# midi10trigger.net
KiCad netlist of a schematic drawn in EAGLE
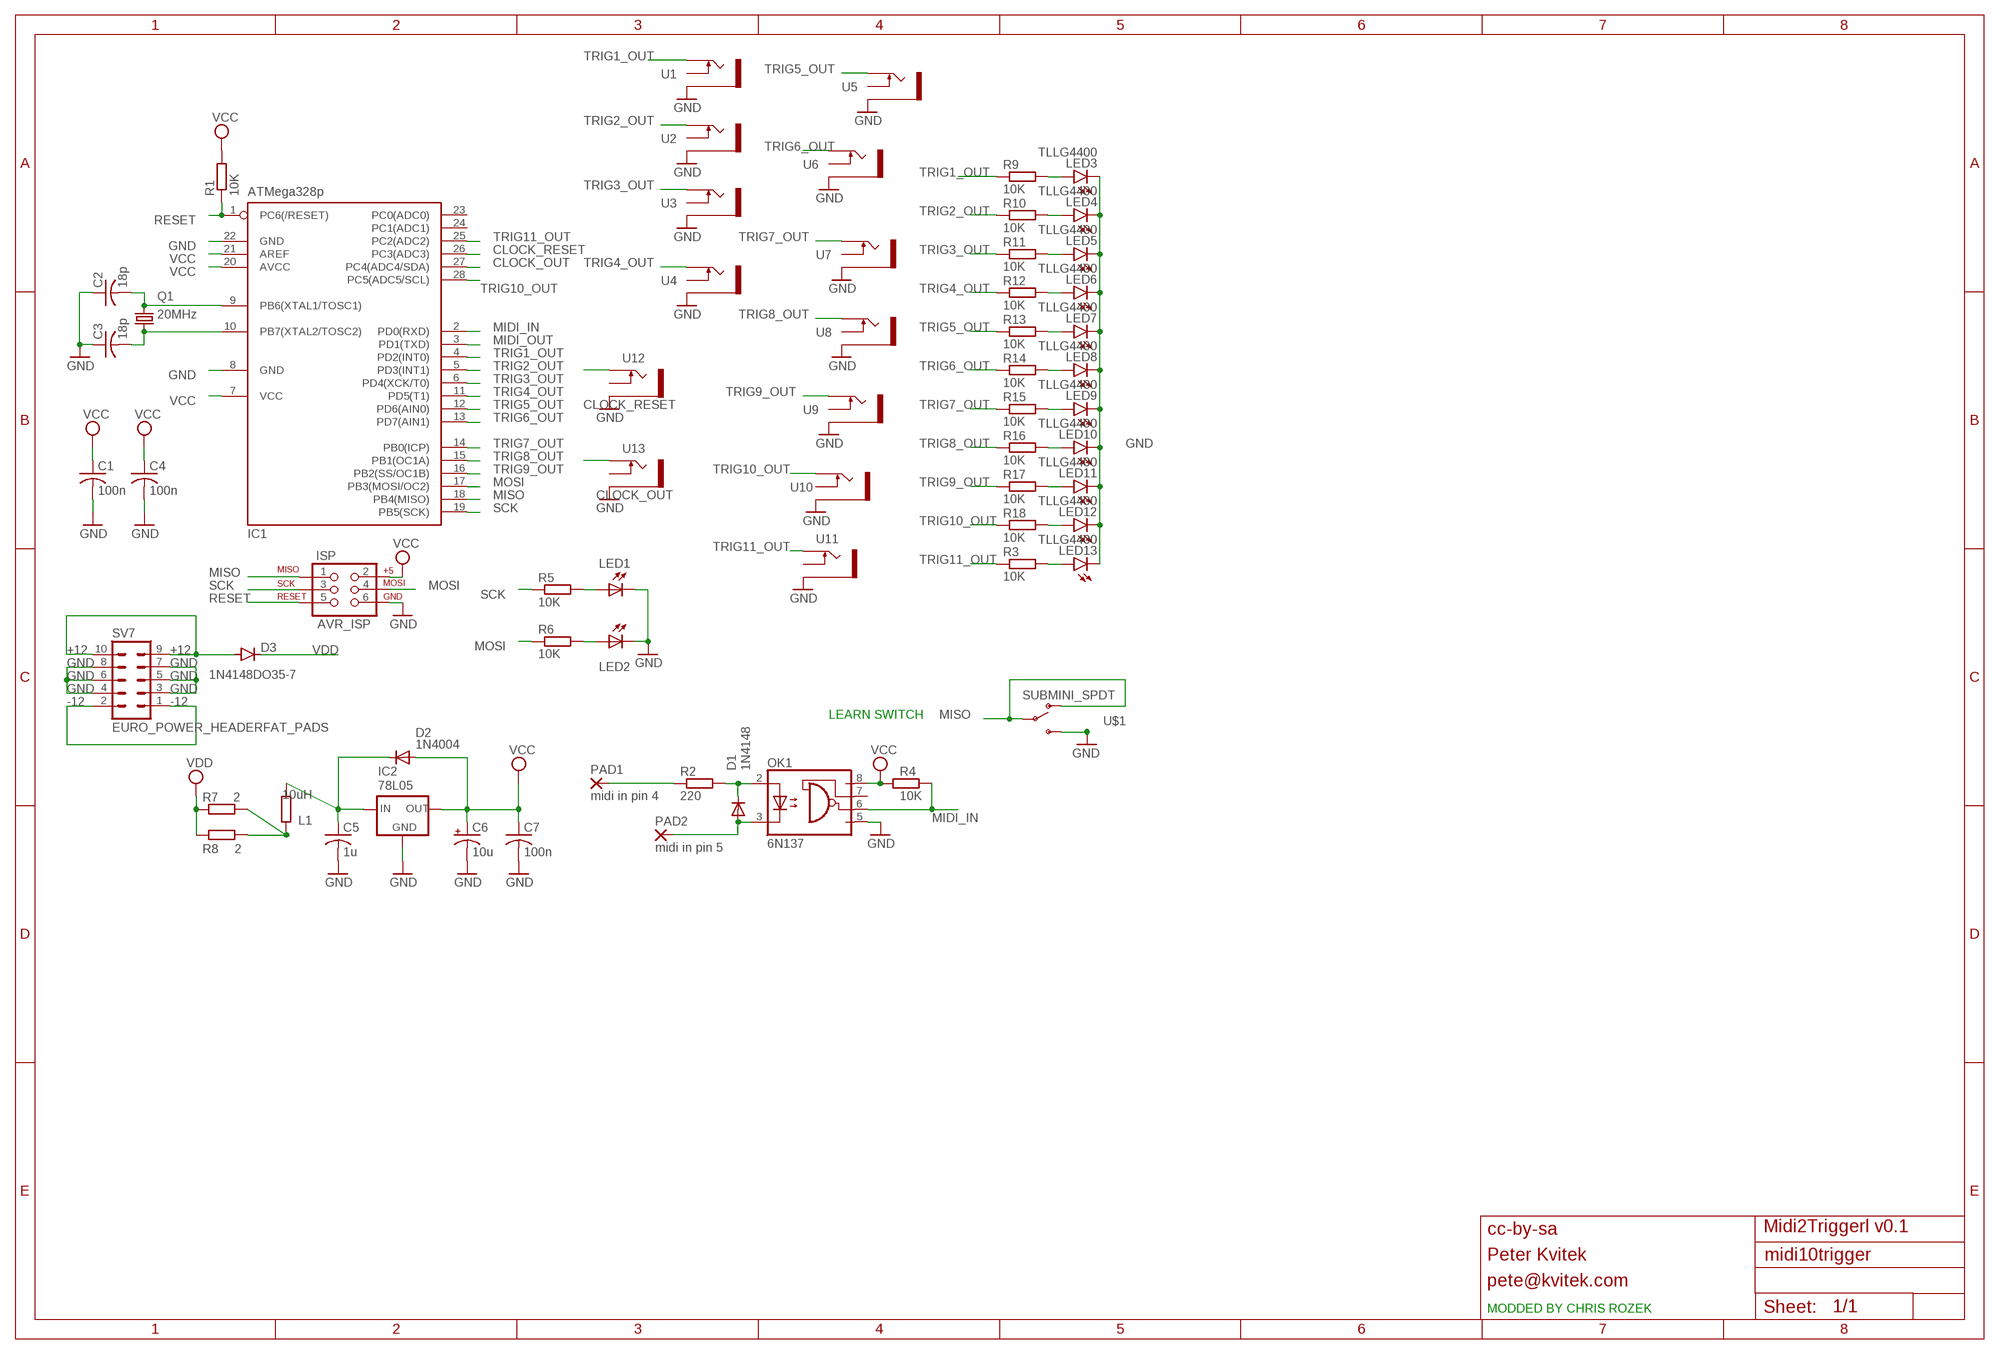
[diagram p0: schematic, sheet 1]

(export (version "E")
  (design (tool "Eeschema 10.0.6"))
  (components
    (comp (ref "C1")
      (value "100n")
      (footprint "eagle-import:C025-025X050")
      (libsource (lib "eagle-import") (part "C-US025-025X050"))
    )
    (comp (ref "C2")
      (value "18p")
      (footprint "eagle-import:C025-025X050")
      (libsource (lib "eagle-import") (part "C-US025-025X050"))
    )
    (comp (ref "C3")
      (value "18p")
      (footprint "eagle-import:C025-025X050")
      (libsource (lib "eagle-import") (part "C-US025-025X050"))
    )
    (comp (ref "C4")
      (value "100n")
      (footprint "eagle-import:C025-025X050")
      (libsource (lib "eagle-import") (part "C-US025-025X050"))
    )
    (comp (ref "C5")
      (value "1u")
      (footprint "eagle-import:C025-025X050")
      (libsource (lib "eagle-import") (part "C-US025-025X050"))
    )
    (comp (ref "C6")
      (value "10u")
      (footprint "eagle-import:E2,5-5")
      (libsource (lib "eagle-import") (part "CPOL-USE2.5-5"))
    )
    (comp (ref "C7")
      (value "100n")
      (footprint "eagle-import:C025-025X050")
      (libsource (lib "eagle-import") (part "C-US025-025X050"))
    )
    (comp (ref "D1")
      (value "1N4148")
      (footprint "eagle-import:D-5")
      (libsource (lib "eagle-import") (part "DIODE-D-5"))
    )
    (comp (ref "D2")
      (value "1N4004")
      (footprint "eagle-import:DO41-10")
      (libsource (lib "eagle-import") (part "1N4004"))
    )
    (comp (ref "D3")
      (value "1N4148DO35-7")
      (footprint "eagle-import:DO35-7")
      (libsource (lib "eagle-import") (part "1N4148DO35-7"))
    )
    (comp (ref "IC1")
      (value "ATMega328p")
      (footprint "eagle-import:DIL28-3")
      (libsource (lib "eagle-import") (part "MEGA8-P"))
    )
    (comp (ref "IC2")
      (value "78L05")
      (footprint "eagle-import:78LXX")
      (libsource (lib "eagle-import") (part "78LXX"))
    )
    (comp (ref "ISP")
      (value "AVR_ISP")
      (footprint "eagle-import:2X3")
      (libsource (lib "eagle-import") (part "AVR_SPI_PRG_6PTH"))
    )
    (comp (ref "L1")
      (value "10uH")
      (footprint "eagle-import:VERTICAL_RESISTOR")
      (libsource (lib "eagle-import") (part "RESISTORVERTICAL"))
    )
    (comp (ref "LED1")
      (value "LED3MM")
      (footprint "eagle-import:LED3MM")
      (libsource (lib "eagle-import") (part "LED3MM"))
    )
    (comp (ref "LED2")
      (value "LED3MM")
      (footprint "eagle-import:LED3MM")
      (libsource (lib "eagle-import") (part "LED3MM"))
    )
    (comp (ref "LED3")
      (value "TLLG4400")
      (footprint "eagle-import:LED3MM")
      (fields (field (name "MF") "VISHAY SEMICONDUCTOR"))
      (libsource (lib "eagle-import") (part "TLLG4400"))
    )
    (comp (ref "LED4")
      (value "TLLG4400")
      (footprint "eagle-import:LED3MM")
      (fields (field (name "MF") "VISHAY SEMICONDUCTOR"))
      (libsource (lib "eagle-import") (part "TLLG4400"))
    )
    (comp (ref "LED5")
      (value "TLLG4400")
      (footprint "eagle-import:LED3MM")
      (fields (field (name "MF") "VISHAY SEMICONDUCTOR"))
      (libsource (lib "eagle-import") (part "TLLG4400"))
    )
    (comp (ref "LED6")
      (value "TLLG4400")
      (footprint "eagle-import:LED3MM")
      (fields (field (name "MF") "VISHAY SEMICONDUCTOR"))
      (libsource (lib "eagle-import") (part "TLLG4400"))
    )
    (comp (ref "LED7")
      (value "TLLG4400")
      (footprint "eagle-import:LED3MM")
      (fields (field (name "MF") "VISHAY SEMICONDUCTOR"))
      (libsource (lib "eagle-import") (part "TLLG4400"))
    )
    (comp (ref "LED8")
      (value "TLLG4400")
      (footprint "eagle-import:LED3MM")
      (fields (field (name "MF") "VISHAY SEMICONDUCTOR"))
      (libsource (lib "eagle-import") (part "TLLG4400"))
    )
    (comp (ref "LED9")
      (value "TLLG4400")
      (footprint "eagle-import:LED3MM")
      (fields (field (name "MF") "VISHAY SEMICONDUCTOR"))
      (libsource (lib "eagle-import") (part "TLLG4400"))
    )
    (comp (ref "LED10")
      (value "TLLG4400")
      (footprint "eagle-import:LED3MM")
      (fields (field (name "MF") "VISHAY SEMICONDUCTOR"))
      (libsource (lib "eagle-import") (part "TLLG4400"))
    )
    (comp (ref "LED11")
      (value "TLLG4400")
      (footprint "eagle-import:LED3MM")
      (fields (field (name "MF") "VISHAY SEMICONDUCTOR"))
      (libsource (lib "eagle-import") (part "TLLG4400"))
    )
    (comp (ref "LED12")
      (value "TLLG4400")
      (footprint "eagle-import:LED3MM")
      (fields (field (name "MF") "VISHAY SEMICONDUCTOR"))
      (libsource (lib "eagle-import") (part "TLLG4400"))
    )
    (comp (ref "LED13")
      (value "TLLG4400")
      (footprint "eagle-import:LED3MM")
      (fields (field (name "MF") "VISHAY SEMICONDUCTOR"))
      (libsource (lib "eagle-import") (part "TLLG4400"))
    )
    (comp (ref "OK1")
      (value "6N137")
      (footprint "eagle-import:DIL08")
      (libsource (lib "eagle-import") (part "6N137"))
    )
    (comp (ref "PAD1")
      (value "midi in pin 4")
      (footprint "eagle-import:2,54_1,1")
      (libsource (lib "eagle-import") (part "2,54/1,1"))
    )
    (comp (ref "PAD2")
      (value "midi in pin 5")
      (footprint "eagle-import:2,54_1,1")
      (libsource (lib "eagle-import") (part "2,54/1,1"))
    )
    (comp (ref "Q1")
      (value "20MHz")
      (footprint "eagle-import:HC49U-V")
      (libsource (lib "eagle-import") (part "CRYSTALHC49U-V"))
    )
    (comp (ref "R1")
      (value "10K")
      (footprint "eagle-import:VERTICAL_RESISTOR")
      (libsource (lib "eagle-import") (part "RESISTORVERTICAL"))
    )
    (comp (ref "R2")
      (value "220")
      (footprint "eagle-import:VERTICAL_RESISTOR")
      (libsource (lib "eagle-import") (part "RESISTORVERTICAL"))
    )
    (comp (ref "R3")
      (value "10K")
      (footprint "eagle-import:VERTICAL_RESISTOR")
      (libsource (lib "eagle-import") (part "RESISTORVERTICAL"))
    )
    (comp (ref "R4")
      (value "10K")
      (footprint "eagle-import:VERTICAL_RESISTOR")
      (libsource (lib "eagle-import") (part "RESISTORVERTICAL"))
    )
    (comp (ref "R5")
      (value "10K")
      (footprint "eagle-import:VERTICAL_RESISTOR")
      (libsource (lib "eagle-import") (part "RESISTORVERTICAL"))
    )
    (comp (ref "R6")
      (value "10K")
      (footprint "eagle-import:VERTICAL_RESISTOR")
      (libsource (lib "eagle-import") (part "RESISTORVERTICAL"))
    )
    (comp (ref "R7")
      (value "2")
      (footprint "eagle-import:VERTICAL_RESISTOR")
      (libsource (lib "eagle-import") (part "RESISTORVERTICAL"))
    )
    (comp (ref "R8")
      (value "2")
      (footprint "eagle-import:VERTICAL_RESISTOR")
      (libsource (lib "eagle-import") (part "RESISTORVERTICAL"))
    )
    (comp (ref "R9")
      (value "10K")
      (footprint "eagle-import:VERTICAL_RESISTOR")
      (libsource (lib "eagle-import") (part "RESISTORVERTICAL"))
    )
    (comp (ref "R10")
      (value "10K")
      (footprint "eagle-import:VERTICAL_RESISTOR")
      (libsource (lib "eagle-import") (part "RESISTORVERTICAL"))
    )
    (comp (ref "R11")
      (value "10K")
      (footprint "eagle-import:VERTICAL_RESISTOR")
      (libsource (lib "eagle-import") (part "RESISTORVERTICAL"))
    )
    (comp (ref "R12")
      (value "10K")
      (footprint "eagle-import:VERTICAL_RESISTOR")
      (libsource (lib "eagle-import") (part "RESISTORVERTICAL"))
    )
    (comp (ref "R13")
      (value "10K")
      (footprint "eagle-import:VERTICAL_RESISTOR")
      (libsource (lib "eagle-import") (part "RESISTORVERTICAL"))
    )
    (comp (ref "R14")
      (value "10K")
      (footprint "eagle-import:VERTICAL_RESISTOR")
      (libsource (lib "eagle-import") (part "RESISTORVERTICAL"))
    )
    (comp (ref "R15")
      (value "10K")
      (footprint "eagle-import:VERTICAL_RESISTOR")
      (libsource (lib "eagle-import") (part "RESISTORVERTICAL"))
    )
    (comp (ref "R16")
      (value "10K")
      (footprint "eagle-import:VERTICAL_RESISTOR")
      (libsource (lib "eagle-import") (part "RESISTORVERTICAL"))
    )
    (comp (ref "R17")
      (value "10K")
      (footprint "eagle-import:VERTICAL_RESISTOR")
      (libsource (lib "eagle-import") (part "RESISTORVERTICAL"))
    )
    (comp (ref "R18")
      (value "10K")
      (footprint "eagle-import:VERTICAL_RESISTOR")
      (libsource (lib "eagle-import") (part "RESISTORVERTICAL"))
    )
    (comp (ref "SV7")
      (value "EURO_POWER_HEADERFAT_PADS")
      (footprint "eagle-import:EURO_PWR_HEADER_FAT")
      (libsource (lib "eagle-import") (part "EURO_POWER_HEADERFAT_PADS"))
    )
    (comp (ref "U$1")
      (value "SUBMINI_SPDT")
      (footprint "eagle-import:SUBMINI_TOGGLE")
      (libsource (lib "eagle-import") (part "SUBMINI_SPDT"))
    )
    (comp (ref "U1")
      (value "THONKICONNNEW")
      (footprint "eagle-import:WQP-PJ301M-12_JACK")
      (libsource (lib "eagle-import") (part "THONKICONNNEW"))
    )
    (comp (ref "U2")
      (value "THONKICONNNEW")
      (footprint "eagle-import:WQP-PJ301M-12_JACK")
      (libsource (lib "eagle-import") (part "THONKICONNNEW"))
    )
    (comp (ref "U3")
      (value "THONKICONNNEW")
      (footprint "eagle-import:WQP-PJ301M-12_JACK")
      (libsource (lib "eagle-import") (part "THONKICONNNEW"))
    )
    (comp (ref "U4")
      (value "THONKICONNNEW")
      (footprint "eagle-import:WQP-PJ301M-12_JACK")
      (libsource (lib "eagle-import") (part "THONKICONNNEW"))
    )
    (comp (ref "U5")
      (value "THONKICONNNEW")
      (footprint "eagle-import:WQP-PJ301M-12_JACK")
      (libsource (lib "eagle-import") (part "THONKICONNNEW"))
    )
    (comp (ref "U6")
      (value "THONKICONNNEW")
      (footprint "eagle-import:WQP-PJ301M-12_JACK")
      (libsource (lib "eagle-import") (part "THONKICONNNEW"))
    )
    (comp (ref "U7")
      (value "THONKICONNNEW")
      (footprint "eagle-import:WQP-PJ301M-12_JACK")
      (libsource (lib "eagle-import") (part "THONKICONNNEW"))
    )
    (comp (ref "U8")
      (value "THONKICONNNEW")
      (footprint "eagle-import:WQP-PJ301M-12_JACK")
      (libsource (lib "eagle-import") (part "THONKICONNNEW"))
    )
    (comp (ref "U9")
      (value "THONKICONNNEW")
      (footprint "eagle-import:WQP-PJ301M-12_JACK")
      (libsource (lib "eagle-import") (part "THONKICONNNEW"))
    )
    (comp (ref "U10")
      (value "THONKICONNNEW")
      (footprint "eagle-import:WQP-PJ301M-12_JACK")
      (libsource (lib "eagle-import") (part "THONKICONNNEW"))
    )
    (comp (ref "U11")
      (value "THONKICONNNEW")
      (footprint "eagle-import:WQP-PJ301M-12_JACK")
      (libsource (lib "eagle-import") (part "THONKICONNNEW"))
    )
    (comp (ref "U12")
      (value "THONKICONNNEW")
      (footprint "eagle-import:WQP-PJ301M-12_JACK")
      (libsource (lib "eagle-import") (part "THONKICONNNEW"))
    )
    (comp (ref "U13")
      (value "THONKICONNNEW")
      (footprint "eagle-import:WQP-PJ301M-12_JACK")
      (libsource (lib "eagle-import") (part "THONKICONNNEW"))
    )
  )
  (nets
    (net (code "1") (name "/+12") (class "Default")
      (node (ref "D3") (pin "A") (pinfunction "A_A") (pintype "passive"))
      (node (ref "SV7") (pin "10") (pinfunction "10_10") (pintype "passive"))
      (node (ref "SV7") (pin "9") (pinfunction "9_9") (pintype "passive"))
    )
    (net (code "2") (name "/-12") (class "Default")
      (node (ref "SV7") (pin "1") (pinfunction "1_1") (pintype "passive"))
      (node (ref "SV7") (pin "2") (pinfunction "2_2") (pintype "passive"))
    )
    (net (code "3") (name "/CLOCK_OUT") (class "Default")
      (node (ref "IC1") (pin "27") (pinfunction "PC4(ADC4/SDA)_27") (pintype "bidirectional"))
      (node (ref "U13") (pin "P$1_TIP") (pinfunction "TIP_P$1_TIP") (pintype "passive"))
    )
    (net (code "4") (name "/CLOCK_RESET") (class "Default")
      (node (ref "IC1") (pin "26") (pinfunction "PC3(ADC3)_26") (pintype "bidirectional"))
      (node (ref "U12") (pin "P$1_TIP") (pinfunction "TIP_P$1_TIP") (pintype "passive"))
    )
    (net (code "5") (name "/MIDI_IN") (class "Default")
      (node (ref "IC1") (pin "2") (pinfunction "PD0(RXD)_2") (pintype "bidirectional"))
      (node (ref "OK1") (pin "6") (pinfunction "VO_6") (pintype "passive"))
      (node (ref "R4") (pin "2") (pinfunction "2_2") (pintype "passive"))
    )
    (net (code "6") (name "/MIDI_OUT") (class "Default")
      (node (ref "IC1") (pin "3") (pinfunction "PD1(TXD)_3") (pintype "bidirectional"))
    )
    (net (code "7") (name "/MISO") (class "Default")
      (node (ref "IC1") (pin "18") (pinfunction "PB4(MISO)_18") (pintype "bidirectional"))
      (node (ref "ISP") (pin "1") (pinfunction "1_1") (pintype "passive"))
      (node (ref "U$1") (pin "1") (pinfunction "O_1") (pintype "passive"))
      (node (ref "U$1") (pin "COM") (pinfunction "COMMON_COM") (pintype "passive"))
    )
    (net (code "8") (name "/MOSI") (class "Default")
      (node (ref "IC1") (pin "17") (pinfunction "PB3(MOSI/OC2)_17") (pintype "bidirectional"))
      (node (ref "ISP") (pin "4") (pinfunction "4_4") (pintype "passive"))
      (node (ref "R6") (pin "1") (pinfunction "1_1") (pintype "passive"))
    )
    (net (code "9") (name "/RESET") (class "Default")
      (node (ref "IC1") (pin "1") (pinfunction "PC6(/RESET)_1") (pintype "bidirectional"))
      (node (ref "ISP") (pin "5") (pinfunction "5_5") (pintype "passive"))
      (node (ref "R1") (pin "1") (pinfunction "1_1") (pintype "passive"))
    )
    (net (code "10") (name "/SCK") (class "Default")
      (node (ref "IC1") (pin "19") (pinfunction "PB5(SCK)_19") (pintype "bidirectional"))
      (node (ref "ISP") (pin "3") (pinfunction "3_3") (pintype "passive"))
      (node (ref "R5") (pin "1") (pinfunction "1_1") (pintype "passive"))
    )
    (net (code "11") (name "/TRIG1_OUT") (class "Default")
      (node (ref "IC1") (pin "4") (pinfunction "PD2(INT0)_4") (pintype "bidirectional"))
      (node (ref "R9") (pin "1") (pinfunction "1_1") (pintype "passive"))
      (node (ref "U1") (pin "P$1_TIP") (pinfunction "TIP_P$1_TIP") (pintype "passive"))
    )
    (net (code "12") (name "/TRIG2_OUT") (class "Default")
      (node (ref "IC1") (pin "5") (pinfunction "PD3(INT1)_5") (pintype "bidirectional"))
      (node (ref "R10") (pin "1") (pinfunction "1_1") (pintype "passive"))
      (node (ref "U2") (pin "P$1_TIP") (pinfunction "TIP_P$1_TIP") (pintype "passive"))
    )
    (net (code "13") (name "/TRIG3_OUT") (class "Default")
      (node (ref "IC1") (pin "6") (pinfunction "PD4(XCK/T0)_6") (pintype "bidirectional"))
      (node (ref "R11") (pin "1") (pinfunction "1_1") (pintype "passive"))
      (node (ref "U3") (pin "P$1_TIP") (pinfunction "TIP_P$1_TIP") (pintype "passive"))
    )
    (net (code "14") (name "/TRIG4_OUT") (class "Default")
      (node (ref "IC1") (pin "11") (pinfunction "PD5(T1)_11") (pintype "bidirectional"))
      (node (ref "R12") (pin "1") (pinfunction "1_1") (pintype "passive"))
      (node (ref "U4") (pin "P$1_TIP") (pinfunction "TIP_P$1_TIP") (pintype "passive"))
    )
    (net (code "15") (name "/TRIG5_OUT") (class "Default")
      (node (ref "IC1") (pin "12") (pinfunction "PD6(AIN0)_12") (pintype "bidirectional"))
      (node (ref "R13") (pin "1") (pinfunction "1_1") (pintype "passive"))
      (node (ref "U5") (pin "P$1_TIP") (pinfunction "TIP_P$1_TIP") (pintype "passive"))
    )
    (net (code "16") (name "/TRIG6_OUT") (class "Default")
      (node (ref "IC1") (pin "13") (pinfunction "PD7(AIN1)_13") (pintype "bidirectional"))
      (node (ref "R14") (pin "1") (pinfunction "1_1") (pintype "passive"))
      (node (ref "U6") (pin "P$1_TIP") (pinfunction "TIP_P$1_TIP") (pintype "passive"))
    )
    (net (code "17") (name "/TRIG7_OUT") (class "Default")
      (node (ref "IC1") (pin "14") (pinfunction "PB0(ICP)_14") (pintype "bidirectional"))
      (node (ref "R15") (pin "1") (pinfunction "1_1") (pintype "passive"))
      (node (ref "U7") (pin "P$1_TIP") (pinfunction "TIP_P$1_TIP") (pintype "passive"))
    )
    (net (code "18") (name "/TRIG8_OUT") (class "Default")
      (node (ref "IC1") (pin "15") (pinfunction "PB1(OC1A)_15") (pintype "bidirectional"))
      (node (ref "R16") (pin "1") (pinfunction "1_1") (pintype "passive"))
      (node (ref "U8") (pin "P$1_TIP") (pinfunction "TIP_P$1_TIP") (pintype "passive"))
    )
    (net (code "19") (name "/TRIG9_OUT") (class "Default")
      (node (ref "IC1") (pin "16") (pinfunction "PB2(SS/OC1B)_16") (pintype "bidirectional"))
      (node (ref "R17") (pin "1") (pinfunction "1_1") (pintype "passive"))
      (node (ref "U9") (pin "P$1_TIP") (pinfunction "TIP_P$1_TIP") (pintype "passive"))
    )
    (net (code "20") (name "/TRIG10_OUT") (class "Default")
      (node (ref "IC1") (pin "28") (pinfunction "PC5(ADC5/SCL)_28") (pintype "bidirectional"))
      (node (ref "R18") (pin "1") (pinfunction "1_1") (pintype "passive"))
      (node (ref "U10") (pin "P$1_TIP") (pinfunction "TIP_P$1_TIP") (pintype "passive"))
    )
    (net (code "21") (name "/TRIG11_OUT") (class "Default")
      (node (ref "IC1") (pin "25") (pinfunction "PC2(ADC2)_25") (pintype "bidirectional"))
      (node (ref "R3") (pin "1") (pinfunction "1_1") (pintype "passive"))
      (node (ref "U11") (pin "P$1_TIP") (pinfunction "TIP_P$1_TIP") (pintype "passive"))
    )
    (net (code "22") (name "GND") (class "Default")
      (node (ref "C1") (pin "2") (pinfunction "2_2") (pintype "passive"))
      (node (ref "C2") (pin "1") (pinfunction "1_1") (pintype "passive"))
      (node (ref "C3") (pin "1") (pinfunction "1_1") (pintype "passive"))
      (node (ref "C4") (pin "2") (pinfunction "2_2") (pintype "passive"))
      (node (ref "C5") (pin "2") (pinfunction "2_2") (pintype "passive"))
      (node (ref "C6") (pin "-") (pinfunction "-_-") (pintype "passive"))
      (node (ref "C7") (pin "2") (pinfunction "2_2") (pintype "passive"))
      (node (ref "IC1") (pin "22") (pinfunction "GND_22") (pintype "power_in"))
      (node (ref "IC1") (pin "8") (pinfunction "GND_8") (pintype "power_in"))
      (node (ref "IC2") (pin "GND") (pinfunction "GND_GND") (pintype "input"))
      (node (ref "ISP") (pin "6") (pinfunction "6_6") (pintype "passive"))
      (node (ref "LED1") (pin "K") (pinfunction "C_K") (pintype "passive"))
      (node (ref "LED10") (pin "K") (pinfunction "C_K") (pintype "passive"))
      (node (ref "LED11") (pin "K") (pinfunction "C_K") (pintype "passive"))
      (node (ref "LED12") (pin "K") (pinfunction "C_K") (pintype "passive"))
      (node (ref "LED13") (pin "K") (pinfunction "C_K") (pintype "passive"))
      (node (ref "LED2") (pin "K") (pinfunction "C_K") (pintype "passive"))
      (node (ref "LED3") (pin "K") (pinfunction "C_K") (pintype "passive"))
      (node (ref "LED4") (pin "K") (pinfunction "C_K") (pintype "passive"))
      (node (ref "LED5") (pin "K") (pinfunction "C_K") (pintype "passive"))
      (node (ref "LED6") (pin "K") (pinfunction "C_K") (pintype "passive"))
      (node (ref "LED7") (pin "K") (pinfunction "C_K") (pintype "passive"))
      (node (ref "LED8") (pin "K") (pinfunction "C_K") (pintype "passive"))
      (node (ref "LED9") (pin "K") (pinfunction "C_K") (pintype "passive"))
      (node (ref "OK1") (pin "5") (pinfunction "GND_5") (pintype "passive"))
      (node (ref "SV7") (pin "3") (pinfunction "3_3") (pintype "passive"))
      (node (ref "SV7") (pin "4") (pinfunction "4_4") (pintype "passive"))
      (node (ref "SV7") (pin "5") (pinfunction "5_5") (pintype "passive"))
      (node (ref "SV7") (pin "6") (pinfunction "6_6") (pintype "passive"))
      (node (ref "SV7") (pin "7") (pinfunction "7_7") (pintype "passive"))
      (node (ref "SV7") (pin "8") (pinfunction "8_8") (pintype "passive"))
      (node (ref "U$1") (pin "3") (pinfunction "S_3") (pintype "passive"))
      (node (ref "U1") (pin "P$3_SLEEVE") (pinfunction "SLEEVE_P$3_SLEEVE") (pintype "passive"))
      (node (ref "U10") (pin "P$3_SLEEVE") (pinfunction "SLEEVE_P$3_SLEEVE") (pintype "passive"))
      (node (ref "U11") (pin "P$3_SLEEVE") (pinfunction "SLEEVE_P$3_SLEEVE") (pintype "passive"))
      (node (ref "U12") (pin "P$3_SLEEVE") (pinfunction "SLEEVE_P$3_SLEEVE") (pintype "passive"))
      (node (ref "U13") (pin "P$3_SLEEVE") (pinfunction "SLEEVE_P$3_SLEEVE") (pintype "passive"))
      (node (ref "U2") (pin "P$3_SLEEVE") (pinfunction "SLEEVE_P$3_SLEEVE") (pintype "passive"))
      (node (ref "U3") (pin "P$3_SLEEVE") (pinfunction "SLEEVE_P$3_SLEEVE") (pintype "passive"))
      (node (ref "U4") (pin "P$3_SLEEVE") (pinfunction "SLEEVE_P$3_SLEEVE") (pintype "passive"))
      (node (ref "U5") (pin "P$3_SLEEVE") (pinfunction "SLEEVE_P$3_SLEEVE") (pintype "passive"))
      (node (ref "U6") (pin "P$3_SLEEVE") (pinfunction "SLEEVE_P$3_SLEEVE") (pintype "passive"))
      (node (ref "U7") (pin "P$3_SLEEVE") (pinfunction "SLEEVE_P$3_SLEEVE") (pintype "passive"))
      (node (ref "U8") (pin "P$3_SLEEVE") (pinfunction "SLEEVE_P$3_SLEEVE") (pintype "passive"))
      (node (ref "U9") (pin "P$3_SLEEVE") (pinfunction "SLEEVE_P$3_SLEEVE") (pintype "passive"))
    )
    (net (code "23") (name "Net-(C5-Pad1)") (class "Default")
      (node (ref "C5") (pin "1") (pinfunction "1_1") (pintype "passive"))
      (node (ref "D2") (pin "C") (pinfunction "C_C") (pintype "passive"))
      (node (ref "IC2") (pin "IN") (pinfunction "IN_IN") (pintype "input"))
      (node (ref "L1") (pin "2") (pinfunction "2_2") (pintype "passive"))
    )
    (net (code "24") (name "Net-(IC1-PB6(XTAL1{slash}TOSC1))") (class "Default")
      (node (ref "C2") (pin "2") (pinfunction "2_2") (pintype "passive"))
      (node (ref "IC1") (pin "9") (pinfunction "PB6(XTAL1/TOSC1)_9") (pintype "bidirectional"))
      (node (ref "Q1") (pin "2") (pinfunction "2_2") (pintype "passive"))
    )
    (net (code "25") (name "Net-(IC1-PB7(XTAL2{slash}TOSC2))") (class "Default")
      (node (ref "C3") (pin "2") (pinfunction "2_2") (pintype "passive"))
      (node (ref "IC1") (pin "10") (pinfunction "PB7(XTAL2/TOSC2)_10") (pintype "bidirectional"))
      (node (ref "Q1") (pin "1") (pinfunction "1_1") (pintype "passive"))
    )
    (net (code "26") (name "Net-(L1-Pad1)") (class "Default")
      (node (ref "L1") (pin "1") (pinfunction "1_1") (pintype "passive"))
      (node (ref "R7") (pin "2") (pinfunction "2_2") (pintype "passive"))
      (node (ref "R8") (pin "2") (pinfunction "2_2") (pintype "passive"))
    )
    (net (code "27") (name "Net-(LED1-PadA)") (class "Default")
      (node (ref "LED1") (pin "A") (pinfunction "A_A") (pintype "passive"))
      (node (ref "R5") (pin "2") (pinfunction "2_2") (pintype "passive"))
    )
    (net (code "28") (name "Net-(LED2-PadA)") (class "Default")
      (node (ref "LED2") (pin "A") (pinfunction "A_A") (pintype "passive"))
      (node (ref "R6") (pin "2") (pinfunction "2_2") (pintype "passive"))
    )
    (net (code "29") (name "Net-(LED3-PadA)") (class "Default")
      (node (ref "LED3") (pin "A") (pinfunction "A_A") (pintype "passive"))
      (node (ref "R9") (pin "2") (pinfunction "2_2") (pintype "passive"))
    )
    (net (code "30") (name "Net-(LED4-PadA)") (class "Default")
      (node (ref "LED4") (pin "A") (pinfunction "A_A") (pintype "passive"))
      (node (ref "R10") (pin "2") (pinfunction "2_2") (pintype "passive"))
    )
    (net (code "31") (name "Net-(LED5-PadA)") (class "Default")
      (node (ref "LED5") (pin "A") (pinfunction "A_A") (pintype "passive"))
      (node (ref "R11") (pin "2") (pinfunction "2_2") (pintype "passive"))
    )
    (net (code "32") (name "Net-(LED6-PadA)") (class "Default")
      (node (ref "LED6") (pin "A") (pinfunction "A_A") (pintype "passive"))
      (node (ref "R12") (pin "2") (pinfunction "2_2") (pintype "passive"))
    )
    (net (code "33") (name "Net-(LED7-PadA)") (class "Default")
      (node (ref "LED7") (pin "A") (pinfunction "A_A") (pintype "passive"))
      (node (ref "R13") (pin "2") (pinfunction "2_2") (pintype "passive"))
    )
    (net (code "34") (name "Net-(LED8-PadA)") (class "Default")
      (node (ref "LED8") (pin "A") (pinfunction "A_A") (pintype "passive"))
      (node (ref "R14") (pin "2") (pinfunction "2_2") (pintype "passive"))
    )
    (net (code "35") (name "Net-(LED9-PadA)") (class "Default")
      (node (ref "LED9") (pin "A") (pinfunction "A_A") (pintype "passive"))
      (node (ref "R15") (pin "2") (pinfunction "2_2") (pintype "passive"))
    )
    (net (code "36") (name "Net-(LED10-PadA)") (class "Default")
      (node (ref "LED10") (pin "A") (pinfunction "A_A") (pintype "passive"))
      (node (ref "R16") (pin "2") (pinfunction "2_2") (pintype "passive"))
    )
    (net (code "37") (name "Net-(LED11-PadA)") (class "Default")
      (node (ref "LED11") (pin "A") (pinfunction "A_A") (pintype "passive"))
      (node (ref "R17") (pin "2") (pinfunction "2_2") (pintype "passive"))
    )
    (net (code "38") (name "Net-(LED12-PadA)") (class "Default")
      (node (ref "LED12") (pin "A") (pinfunction "A_A") (pintype "passive"))
      (node (ref "R18") (pin "2") (pinfunction "2_2") (pintype "passive"))
    )
    (net (code "39") (name "Net-(LED13-PadA)") (class "Default")
      (node (ref "LED13") (pin "A") (pinfunction "A_A") (pintype "passive"))
      (node (ref "R3") (pin "2") (pinfunction "2_2") (pintype "passive"))
    )
    (net (code "40") (name "Net-(OK1-A)") (class "Default")
      (node (ref "D1") (pin "C") (pinfunction "C_C") (pintype "passive"))
      (node (ref "OK1") (pin "2") (pinfunction "A_2") (pintype "passive"))
      (node (ref "R2") (pin "2") (pinfunction "2_2") (pintype "passive"))
    )
    (net (code "41") (name "Net-(OK1-C)") (class "Default")
      (node (ref "D1") (pin "A") (pinfunction "A_A") (pintype "passive"))
      (node (ref "OK1") (pin "3") (pinfunction "C_3") (pintype "passive"))
      (node (ref "PAD2") (pin "1") (pinfunction "P_1") (pintype "passive"))
    )
    (net (code "42") (name "Net-(PAD1-P)") (class "Default")
      (node (ref "PAD1") (pin "1") (pinfunction "P_1") (pintype "passive"))
      (node (ref "R2") (pin "1") (pinfunction "1_1") (pintype "passive"))
    )
    (net (code "43") (name "VCC") (class "Default")
      (node (ref "C1") (pin "1") (pinfunction "1_1") (pintype "passive"))
      (node (ref "C4") (pin "1") (pinfunction "1_1") (pintype "passive"))
      (node (ref "C6") (pin "+") (pinfunction "+_+") (pintype "passive"))
      (node (ref "C7") (pin "1") (pinfunction "1_1") (pintype "passive"))
      (node (ref "D2") (pin "A") (pinfunction "A_A") (pintype "passive"))
      (node (ref "IC1") (pin "20") (pinfunction "AVCC_20") (pintype "power_in"))
      (node (ref "IC1") (pin "21") (pinfunction "AREF_21") (pintype "passive"))
      (node (ref "IC1") (pin "7") (pinfunction "VCC_7") (pintype "power_in"))
      (node (ref "IC2") (pin "OUT") (pinfunction "OUT_OUT") (pintype "passive"))
      (node (ref "ISP") (pin "2") (pinfunction "2_2") (pintype "passive"))
      (node (ref "OK1") (pin "8") (pinfunction "VCC_8") (pintype "passive"))
      (node (ref "R1") (pin "2") (pinfunction "2_2") (pintype "passive"))
      (node (ref "R4") (pin "1") (pinfunction "1_1") (pintype "passive"))
    )
    (net (code "44") (name "VDD") (class "Default")
      (node (ref "D3") (pin "C") (pinfunction "C_C") (pintype "passive"))
      (node (ref "R7") (pin "1") (pinfunction "1_1") (pintype "passive"))
      (node (ref "R8") (pin "1") (pinfunction "1_1") (pintype "passive"))
    )
    (net (code "45") (name "unconnected-(IC1-PC0(ADC0)-Pad23)") (class "Default")
      (node (ref "IC1") (pin "23") (pinfunction "PC0(ADC0)_23") (pintype "bidirectional"))
    )
    (net (code "46") (name "unconnected-(IC1-PC1(ADC1)-Pad24)") (class "Default")
      (node (ref "IC1") (pin "24") (pinfunction "PC1(ADC1)_24") (pintype "bidirectional"))
    )
    (net (code "47") (name "unconnected-(OK1-VE-Pad7)") (class "Default")
      (node (ref "OK1") (pin "7") (pinfunction "VE_7") (pintype "passive"))
    )
    (net (code "48") (name "unconnected-(U1-SWITCH-PadP$2_SWITCH)") (class "Default")
      (node (ref "U1") (pin "P$2_SWITCH") (pinfunction "SWITCH_P$2_SWITCH") (pintype "passive"))
    )
    (net (code "49") (name "unconnected-(U2-SWITCH-PadP$2_SWITCH)") (class "Default")
      (node (ref "U2") (pin "P$2_SWITCH") (pinfunction "SWITCH_P$2_SWITCH") (pintype "passive"))
    )
    (net (code "50") (name "unconnected-(U3-SWITCH-PadP$2_SWITCH)") (class "Default")
      (node (ref "U3") (pin "P$2_SWITCH") (pinfunction "SWITCH_P$2_SWITCH") (pintype "passive"))
    )
    (net (code "51") (name "unconnected-(U4-SWITCH-PadP$2_SWITCH)") (class "Default")
      (node (ref "U4") (pin "P$2_SWITCH") (pinfunction "SWITCH_P$2_SWITCH") (pintype "passive"))
    )
    (net (code "52") (name "unconnected-(U5-SWITCH-PadP$2_SWITCH)") (class "Default")
      (node (ref "U5") (pin "P$2_SWITCH") (pinfunction "SWITCH_P$2_SWITCH") (pintype "passive"))
    )
    (net (code "53") (name "unconnected-(U6-SWITCH-PadP$2_SWITCH)") (class "Default")
      (node (ref "U6") (pin "P$2_SWITCH") (pinfunction "SWITCH_P$2_SWITCH") (pintype "passive"))
    )
    (net (code "54") (name "unconnected-(U7-SWITCH-PadP$2_SWITCH)") (class "Default")
      (node (ref "U7") (pin "P$2_SWITCH") (pinfunction "SWITCH_P$2_SWITCH") (pintype "passive"))
    )
    (net (code "55") (name "unconnected-(U8-SWITCH-PadP$2_SWITCH)") (class "Default")
      (node (ref "U8") (pin "P$2_SWITCH") (pinfunction "SWITCH_P$2_SWITCH") (pintype "passive"))
    )
    (net (code "56") (name "unconnected-(U9-SWITCH-PadP$2_SWITCH)") (class "Default")
      (node (ref "U9") (pin "P$2_SWITCH") (pinfunction "SWITCH_P$2_SWITCH") (pintype "passive"))
    )
    (net (code "57") (name "unconnected-(U10-SWITCH-PadP$2_SWITCH)") (class "Default")
      (node (ref "U10") (pin "P$2_SWITCH") (pinfunction "SWITCH_P$2_SWITCH") (pintype "passive"))
    )
    (net (code "58") (name "unconnected-(U11-SWITCH-PadP$2_SWITCH)") (class "Default")
      (node (ref "U11") (pin "P$2_SWITCH") (pinfunction "SWITCH_P$2_SWITCH") (pintype "passive"))
    )
    (net (code "59") (name "unconnected-(U12-SWITCH-PadP$2_SWITCH)") (class "Default")
      (node (ref "U12") (pin "P$2_SWITCH") (pinfunction "SWITCH_P$2_SWITCH") (pintype "passive"))
    )
    (net (code "60") (name "unconnected-(U13-SWITCH-PadP$2_SWITCH)") (class "Default")
      (node (ref "U13") (pin "P$2_SWITCH") (pinfunction "SWITCH_P$2_SWITCH") (pintype "passive"))
    )
  )
)
